# 100kw-DC-Motor-ESC.net
KiCad netlist of a schematic drawn in EAGLE
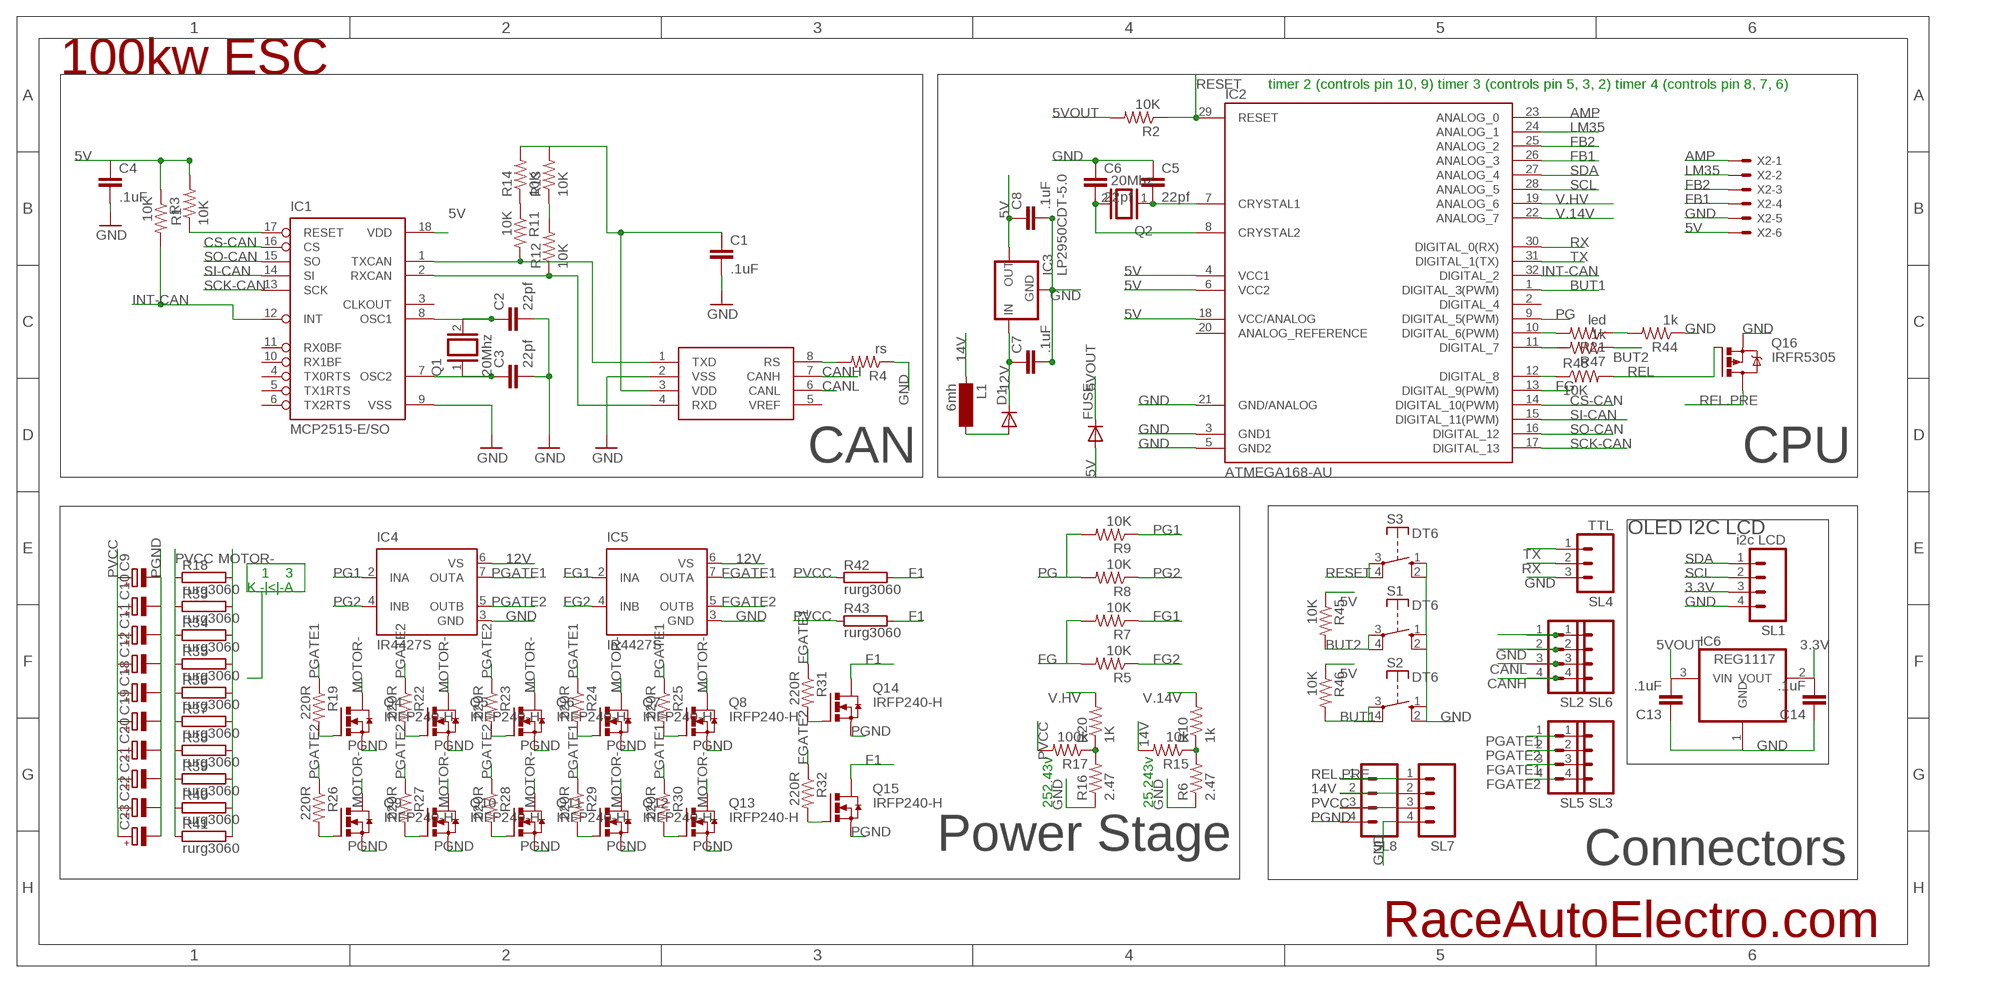
[diagram p0: schematic, sheet 1]

(export (version "E")
  (design (tool "Eeschema 10.0.6"))
  (components
    (comp (ref "C1")
      (value ".1uF")
      (footprint "eagle-import:0805")
      (libsource (lib "eagle-import") (part "CAP0805"))
    )
    (comp (ref "C2")
      (value "22pf")
      (footprint "eagle-import:0805")
      (libsource (lib "eagle-import") (part "CAP0805"))
    )
    (comp (ref "C3")
      (value "22pf")
      (footprint "eagle-import:0805")
      (libsource (lib "eagle-import") (part "CAP0805"))
    )
    (comp (ref "C4")
      (value ".1uF")
      (footprint "eagle-import:1210")
      (libsource (lib "eagle-import") (part "CAP1210"))
    )
    (comp (ref "C5")
      (value "22pf")
      (footprint "eagle-import:0805")
      (libsource (lib "eagle-import") (part "CAP0805"))
    )
    (comp (ref "C6")
      (value "22pf")
      (footprint "eagle-import:0805")
      (libsource (lib "eagle-import") (part "CAP0805"))
    )
    (comp (ref "C7")
      (value ".1uF")
      (footprint "eagle-import:1210")
      (libsource (lib "eagle-import") (part "CAP1210"))
    )
    (comp (ref "C8")
      (value ".1uF")
      (footprint "eagle-import:1210")
      (libsource (lib "eagle-import") (part "CAP1210"))
    )
    (comp (ref "C9")
      (value "CPOL-EUE10-35")
      (footprint "eagle-import:EB35D")
      (libsource (lib "eagle-import") (part "CPOL-EUE10-35"))
    )
    (comp (ref "C10")
      (value "CPOL-EUE10-35")
      (footprint "eagle-import:EB35D")
      (libsource (lib "eagle-import") (part "CPOL-EUE10-35"))
    )
    (comp (ref "C11")
      (value "CPOL-EUE10-35")
      (footprint "eagle-import:EB35D")
      (libsource (lib "eagle-import") (part "CPOL-EUE10-35"))
    )
    (comp (ref "C12")
      (value "CPOL-EUE10-35")
      (footprint "eagle-import:EB35D")
      (libsource (lib "eagle-import") (part "CPOL-EUE10-35"))
    )
    (comp (ref "C13")
      (value ".1uF")
      (footprint "eagle-import:1210")
      (libsource (lib "eagle-import") (part "CAP1210"))
    )
    (comp (ref "C14")
      (value ".1uF")
      (footprint "eagle-import:1210")
      (libsource (lib "eagle-import") (part "CAP1210"))
    )
    (comp (ref "C18")
      (value "CPOL-EUE10-35")
      (footprint "eagle-import:EB35D")
      (libsource (lib "eagle-import") (part "CPOL-EUE10-35"))
    )
    (comp (ref "C19")
      (value "CPOL-EUE10-35")
      (footprint "eagle-import:EB35D")
      (libsource (lib "eagle-import") (part "CPOL-EUE10-35"))
    )
    (comp (ref "C20")
      (value "CPOL-EUE10-35")
      (footprint "eagle-import:EB35D")
      (libsource (lib "eagle-import") (part "CPOL-EUE10-35"))
    )
    (comp (ref "C21")
      (value "CPOL-EUE10-35")
      (footprint "eagle-import:EB35D")
      (libsource (lib "eagle-import") (part "CPOL-EUE10-35"))
    )
    (comp (ref "C22")
      (value "CPOL-EUE10-35")
      (footprint "eagle-import:EB35D")
      (libsource (lib "eagle-import") (part "CPOL-EUE10-35"))
    )
    (comp (ref "C23")
      (value "CPOL-EUE10-35")
      (footprint "eagle-import:EB35D")
      (libsource (lib "eagle-import") (part "CPOL-EUE10-35"))
    )
    (comp (ref "D1")
      (value "DIODE-DO-214AC")
      (footprint "eagle-import:DO-214AC")
      (libsource (lib "eagle-import") (part "DIODE-DO-214AC"))
    )
    (comp (ref "FUSE")
      (value "DIODE-DO-214AC")
      (footprint "eagle-import:DO-214AC")
      (libsource (lib "eagle-import") (part "DIODE-DO-214AC"))
    )
    (comp (ref "IC1")
      (value "MCP2515-E/SO")
      (footprint "eagle-import:SO18L")
      (libsource (lib "eagle-import") (part "MCP2515-E/SO"))
    )
    (comp (ref "IC2")
      (value "ATMEGA168-AU")
      (footprint "eagle-import:TQFP32-08")
      (libsource (lib "eagle-import") (part "ATMEGA168-AU"))
    )
    (comp (ref "IC3")
      (value "LP2950CDT-5.0")
      (footprint "eagle-import:DPACK")
      (libsource (lib "eagle-import") (part "LP2950?CDT-5.0"))
    )
    (comp (ref "IC4")
      (value "IR4427S")
      (footprint "eagle-import:SO08")
      (fields (field (name "MF") "INTERNATIONAL RECTIFIER(IR)") (field (name "MPN") "IR4427STRPBF"))
      (libsource (lib "eagle-import") (part "IR4427S"))
    )
    (comp (ref "IC5")
      (value "IR4427S")
      (footprint "eagle-import:SO08")
      (fields (field (name "MF") "INTERNATIONAL RECTIFIER(IR)") (field (name "MPN") "IR4427STRPBF"))
      (libsource (lib "eagle-import") (part "IR4427S"))
    )
    (comp (ref "IC6")
      (value "REG1117")
      (footprint "eagle-import:SOT223")
      (libsource (lib "eagle-import") (part "REG1117"))
    )
    (comp (ref "L1")
      (value "6mh")
      (footprint "eagle-import:MS85")
      (libsource (lib "eagle-import") (part "MS85"))
    )
    (comp (ref "Q1")
      (value "20Mhz")
      (footprint "eagle-import:QS")
      (libsource (lib "eagle-import") (part "XTAL/S"))
    )
    (comp (ref "Q2")
      (value "20Mhz")
      (footprint "eagle-import:QS")
      (libsource (lib "eagle-import") (part "XTAL/S"))
    )
    (comp (ref "Q4")
      (value "IRFP240-H")
      (footprint "eagle-import:TO247BH")
      (libsource (lib "eagle-import") (part "IRFP240-H"))
    )
    (comp (ref "Q5")
      (value "IRFP240-H")
      (footprint "eagle-import:TO247BH")
      (libsource (lib "eagle-import") (part "IRFP240-H"))
    )
    (comp (ref "Q6")
      (value "IRFP240-H")
      (footprint "eagle-import:TO247BH")
      (libsource (lib "eagle-import") (part "IRFP240-H"))
    )
    (comp (ref "Q7")
      (value "IRFP240-H")
      (footprint "eagle-import:TO247BH")
      (libsource (lib "eagle-import") (part "IRFP240-H"))
    )
    (comp (ref "Q8")
      (value "IRFP240-H")
      (footprint "eagle-import:TO247BH")
      (libsource (lib "eagle-import") (part "IRFP240-H"))
    )
    (comp (ref "Q9")
      (value "IRFP240-H")
      (footprint "eagle-import:TO247BH")
      (libsource (lib "eagle-import") (part "IRFP240-H"))
    )
    (comp (ref "Q10")
      (value "IRFP240-H")
      (footprint "eagle-import:TO247BH")
      (libsource (lib "eagle-import") (part "IRFP240-H"))
    )
    (comp (ref "Q11")
      (value "IRFP240-H")
      (footprint "eagle-import:TO247BH")
      (libsource (lib "eagle-import") (part "IRFP240-H"))
    )
    (comp (ref "Q12")
      (value "IRFP240-H")
      (footprint "eagle-import:TO247BH")
      (libsource (lib "eagle-import") (part "IRFP240-H"))
    )
    (comp (ref "Q13")
      (value "IRFP240-H")
      (footprint "eagle-import:TO247BH")
      (libsource (lib "eagle-import") (part "IRFP240-H"))
    )
    (comp (ref "Q14")
      (value "IRFP240-H")
      (footprint "eagle-import:TO247BH")
      (libsource (lib "eagle-import") (part "IRFP240-H"))
    )
    (comp (ref "Q15")
      (value "IRFP240-H")
      (footprint "eagle-import:TO247BH")
      (libsource (lib "eagle-import") (part "IRFP240-H"))
    )
    (comp (ref "Q16")
      (value "IRFR5305")
      (footprint "eagle-import:D-PAK_TO252AA")
      (libsource (lib "eagle-import") (part "IRF?5305R"))
    )
    (comp (ref "R1")
      (value "10K")
      (footprint "eagle-import:0805")
      (libsource (lib "eagle-import") (part "RESISTOR0805-RES"))
    )
    (comp (ref "R2")
      (value "10K")
      (footprint "eagle-import:1206")
      (libsource (lib "eagle-import") (part "RESISTOR1206"))
    )
    (comp (ref "R3")
      (value "10K")
      (footprint "eagle-import:0805")
      (libsource (lib "eagle-import") (part "RESISTOR0805-RES"))
    )
    (comp (ref "R4")
      (value "rs")
      (footprint "eagle-import:0805")
      (libsource (lib "eagle-import") (part "RESISTOR0805-RES"))
    )
    (comp (ref "R5")
      (value "10K")
      (footprint "eagle-import:0805")
      (libsource (lib "eagle-import") (part "RESISTOR0805-RES"))
    )
    (comp (ref "R6")
      (value "2.47")
      (footprint "eagle-import:0805")
      (libsource (lib "eagle-import") (part "RESISTOR0805-RES"))
    )
    (comp (ref "R7")
      (value "10K")
      (footprint "eagle-import:0805")
      (libsource (lib "eagle-import") (part "RESISTOR0805-RES"))
    )
    (comp (ref "R8")
      (value "10K")
      (footprint "eagle-import:0805")
      (libsource (lib "eagle-import") (part "RESISTOR0805-RES"))
    )
    (comp (ref "R9")
      (value "10K")
      (footprint "eagle-import:0805")
      (libsource (lib "eagle-import") (part "RESISTOR0805-RES"))
    )
    (comp (ref "R10")
      (value "1k")
      (footprint "eagle-import:0805")
      (libsource (lib "eagle-import") (part "RESISTOR0805-RES"))
    )
    (comp (ref "R11")
      (value "10K")
      (footprint "eagle-import:0805")
      (libsource (lib "eagle-import") (part "RESISTOR0805-RES"))
    )
    (comp (ref "R12")
      (value "10K")
      (footprint "eagle-import:0805")
      (libsource (lib "eagle-import") (part "RESISTOR0805-RES"))
    )
    (comp (ref "R13")
      (value "10K")
      (footprint "eagle-import:0805")
      (libsource (lib "eagle-import") (part "RESISTOR0805-RES"))
    )
    (comp (ref "R14")
      (value "10K")
      (footprint "eagle-import:0805")
      (libsource (lib "eagle-import") (part "RESISTOR0805-RES"))
    )
    (comp (ref "R15")
      (value "10k")
      (footprint "eagle-import:0805")
      (libsource (lib "eagle-import") (part "RESISTOR0805-RES"))
    )
    (comp (ref "R16")
      (value "2.47")
      (footprint "eagle-import:0805")
      (libsource (lib "eagle-import") (part "RESISTOR0805-RES"))
    )
    (comp (ref "R17")
      (value "100k")
      (footprint "eagle-import:0805")
      (libsource (lib "eagle-import") (part "RESISTOR0805-RES"))
    )
    (comp (ref "R18")
      (value "rurg3060")
      (footprint "eagle-import:TO-247-2H")
      (libsource (lib "eagle-import") (part "RMG100-H"))
    )
    (comp (ref "R19")
      (value "220R")
      (footprint "eagle-import:0805")
      (libsource (lib "eagle-import") (part "RESISTOR0805-RES"))
    )
    (comp (ref "R20")
      (value "1K")
      (footprint "eagle-import:0805")
      (libsource (lib "eagle-import") (part "RESISTOR0805-RES"))
    )
    (comp (ref "R21")
      (value "led")
      (footprint "eagle-import:1206")
      (libsource (lib "eagle-import") (part "RESISTOR1206"))
    )
    (comp (ref "R22")
      (value "220R")
      (footprint "eagle-import:0805")
      (libsource (lib "eagle-import") (part "RESISTOR0805-RES"))
    )
    (comp (ref "R23")
      (value "220R")
      (footprint "eagle-import:0805")
      (libsource (lib "eagle-import") (part "RESISTOR0805-RES"))
    )
    (comp (ref "R24")
      (value "220R")
      (footprint "eagle-import:0805")
      (libsource (lib "eagle-import") (part "RESISTOR0805-RES"))
    )
    (comp (ref "R25")
      (value "220R")
      (footprint "eagle-import:0805")
      (libsource (lib "eagle-import") (part "RESISTOR0805-RES"))
    )
    (comp (ref "R26")
      (value "220R")
      (footprint "eagle-import:0805")
      (libsource (lib "eagle-import") (part "RESISTOR0805-RES"))
    )
    (comp (ref "R27")
      (value "220R")
      (footprint "eagle-import:0805")
      (libsource (lib "eagle-import") (part "RESISTOR0805-RES"))
    )
    (comp (ref "R28")
      (value "220R")
      (footprint "eagle-import:0805")
      (libsource (lib "eagle-import") (part "RESISTOR0805-RES"))
    )
    (comp (ref "R29")
      (value "220R")
      (footprint "eagle-import:0805")
      (libsource (lib "eagle-import") (part "RESISTOR0805-RES"))
    )
    (comp (ref "R30")
      (value "220R")
      (footprint "eagle-import:0805")
      (libsource (lib "eagle-import") (part "RESISTOR0805-RES"))
    )
    (comp (ref "R31")
      (value "220R")
      (footprint "eagle-import:0805")
      (libsource (lib "eagle-import") (part "RESISTOR0805-RES"))
    )
    (comp (ref "R32")
      (value "220R")
      (footprint "eagle-import:0805")
      (libsource (lib "eagle-import") (part "RESISTOR0805-RES"))
    )
    (comp (ref "R33")
      (value "rurg3060")
      (footprint "eagle-import:TO-247-2H")
      (libsource (lib "eagle-import") (part "RMG100-H"))
    )
    (comp (ref "R34")
      (value "rurg3060")
      (footprint "eagle-import:TO-247-2H")
      (libsource (lib "eagle-import") (part "RMG100-H"))
    )
    (comp (ref "R35")
      (value "rurg3060")
      (footprint "eagle-import:TO-247-2H")
      (libsource (lib "eagle-import") (part "RMG100-H"))
    )
    (comp (ref "R36")
      (value "rurg3060")
      (footprint "eagle-import:TO-247-2H")
      (libsource (lib "eagle-import") (part "RMG100-H"))
    )
    (comp (ref "R37")
      (value "rurg3060")
      (footprint "eagle-import:TO-247-2H")
      (libsource (lib "eagle-import") (part "RMG100-H"))
    )
    (comp (ref "R38")
      (value "rurg3060")
      (footprint "eagle-import:TO-247-2H")
      (libsource (lib "eagle-import") (part "RMG100-H"))
    )
    (comp (ref "R39")
      (value "rurg3060")
      (footprint "eagle-import:TO-247-2H")
      (libsource (lib "eagle-import") (part "RMG100-H"))
    )
    (comp (ref "R40")
      (value "rurg3060")
      (footprint "eagle-import:TO-247-2H")
      (libsource (lib "eagle-import") (part "RMG100-H"))
    )
    (comp (ref "R41")
      (value "rurg3060")
      (footprint "eagle-import:TO-247-2H")
      (libsource (lib "eagle-import") (part "RMG100-H"))
    )
    (comp (ref "R42")
      (value "rurg3060")
      (footprint "eagle-import:TO-247-2H")
      (libsource (lib "eagle-import") (part "RMG100-H"))
    )
    (comp (ref "R43")
      (value "rurg3060")
      (footprint "eagle-import:TO-247-2H")
      (libsource (lib "eagle-import") (part "RMG100-H"))
    )
    (comp (ref "R44")
      (value "1k")
      (footprint "eagle-import:0805")
      (libsource (lib "eagle-import") (part "RESISTOR0805-RES"))
    )
    (comp (ref "R45")
      (value "10K")
      (footprint "eagle-import:0805")
      (libsource (lib "eagle-import") (part "RESISTOR0805-RES"))
    )
    (comp (ref "R46")
      (value "10K")
      (footprint "eagle-import:0805")
      (libsource (lib "eagle-import") (part "RESISTOR0805-RES"))
    )
    (comp (ref "R47")
      (value "1k")
      (footprint "eagle-import:0805")
      (libsource (lib "eagle-import") (part "RESISTOR0805-RES"))
    )
    (comp (ref "R48")
      (value "10K")
      (footprint "eagle-import:0805")
      (libsource (lib "eagle-import") (part "RESISTOR0805-RES"))
    )
    (comp (ref "S1")
      (value "DT6")
      (footprint "eagle-import:DT6")
      (libsource (lib "eagle-import") (part "DT6"))
    )
    (comp (ref "S2")
      (value "DT6")
      (footprint "eagle-import:DT6")
      (libsource (lib "eagle-import") (part "DT6"))
    )
    (comp (ref "S3")
      (value "DT6")
      (footprint "eagle-import:DT6")
      (libsource (lib "eagle-import") (part "DT6"))
    )
    (comp (ref "SL1")
      (value "i2c LCD")
      (footprint "eagle-import:04P")
      (libsource (lib "eagle-import") (part "M04"))
    )
    (comp (ref "SL2")
      (value "M04")
      (footprint "eagle-import:04P")
      (libsource (lib "eagle-import") (part "M04"))
    )
    (comp (ref "SL3")
      (value "M04")
      (footprint "eagle-import:04P")
      (libsource (lib "eagle-import") (part "M04"))
    )
    (comp (ref "SL4")
      (value "TTL")
      (footprint "eagle-import:03P")
      (libsource (lib "eagle-import") (part "M03"))
    )
    (comp (ref "SL5")
      (value "M04")
      (footprint "eagle-import:04P")
      (libsource (lib "eagle-import") (part "M04"))
    )
    (comp (ref "SL6")
      (value "M04")
      (footprint "eagle-import:04P")
      (libsource (lib "eagle-import") (part "M04"))
    )
    (comp (ref "SL7")
      (value "M04")
      (footprint "eagle-import:04P")
      (libsource (lib "eagle-import") (part "M04"))
    )
    (comp (ref "SL8")
      (value "M04")
      (footprint "eagle-import:04P")
      (libsource (lib "eagle-import") (part "M04"))
    )
    (comp (ref "U1")
      (value "MCP2551")
      (footprint "eagle-import:SO08")
      (libsource (lib "eagle-import") (part "MCP2551"))
    )
    (comp (ref "X2")
      (value "22-23-2061")
      (footprint "eagle-import:22-23-2061")
      (fields (field (name "MF") "MOLEX"))
      (libsource (lib "eagle-import") (part "22-23-2061"))
    )
  )
  (nets
    (net (code "1") (name "/3.3V") (class "Default")
      (node (ref "C14") (pin "2") (pinfunction "2_2") (pintype "passive"))
      (node (ref "IC6") (pin "2") (pinfunction "VOUT_2") (pintype "output"))
      (node (ref "SL1") (pin "3") (pinfunction "3_3") (pintype "passive"))
    )
    (net (code "2") (name "/5V") (class "Default")
      (node (ref "C1") (pin "1") (pinfunction "1_1") (pintype "passive"))
      (node (ref "C4") (pin "1") (pinfunction "1_1") (pintype "passive"))
      (node (ref "C8") (pin "1") (pinfunction "1_1") (pintype "passive"))
      (node (ref "FUSE") (pin "A") (pinfunction "A_A") (pintype "passive"))
      (node (ref "IC1") (pin "18") (pinfunction "VDD_18") (pintype "power_in"))
      (node (ref "IC2") (pin "18") (pinfunction "VCC/ANALOG_18") (pintype "passive"))
      (node (ref "IC2") (pin "4") (pinfunction "VCC1_4") (pintype "power_in"))
      (node (ref "IC2") (pin "6") (pinfunction "VCC2_6") (pintype "power_in"))
      (node (ref "IC3") (pin "3") (pinfunction "OUT_3") (pintype "passive"))
      (node (ref "R1") (pin "2") (pinfunction "2_2") (pintype "passive"))
      (node (ref "R13") (pin "2") (pinfunction "2_2") (pintype "passive"))
      (node (ref "R14") (pin "2") (pinfunction "2_2") (pintype "passive"))
      (node (ref "R3") (pin "1") (pinfunction "1_1") (pintype "passive"))
      (node (ref "R45") (pin "1") (pinfunction "1_1") (pintype "passive"))
      (node (ref "R46") (pin "1") (pinfunction "1_1") (pintype "passive"))
      (node (ref "U1") (pin "3") (pinfunction "VDD_3") (pintype "bidirectional"))
      (node (ref "X2") (pin "6") (pinfunction "S_6") (pintype "passive"))
    )
    (net (code "3") (name "/5VOUT") (class "Default")
      (node (ref "C13") (pin "2") (pinfunction "2_2") (pintype "passive"))
      (node (ref "FUSE") (pin "C") (pinfunction "C_C") (pintype "passive"))
      (node (ref "IC6") (pin "3") (pinfunction "VIN_3") (pintype "input"))
      (node (ref "R2") (pin "2") (pinfunction "2_2") (pintype "passive"))
    )
    (net (code "4") (name "/12V") (class "Default")
      (node (ref "C7") (pin "1") (pinfunction "1_1") (pintype "passive"))
      (node (ref "D1") (pin "C") (pinfunction "C_C") (pintype "passive"))
      (node (ref "IC3") (pin "1") (pinfunction "IN_1") (pintype "input"))
      (node (ref "IC4") (pin "6") (pinfunction "VS_6") (pintype "power_in"))
      (node (ref "IC5") (pin "6") (pinfunction "VS_6") (pintype "power_in"))
    )
    (net (code "5") (name "/14V") (class "Default")
      (node (ref "L1") (pin "1") (pinfunction "1_1") (pintype "passive"))
      (node (ref "R15") (pin "2") (pinfunction "2_2") (pintype "passive"))
      (node (ref "SL7") (pin "2") (pinfunction "2_2") (pintype "passive"))
      (node (ref "SL8") (pin "2") (pinfunction "2_2") (pintype "passive"))
    )
    (net (code "6") (name "/AMP") (class "Default")
      (node (ref "IC2") (pin "23") (pinfunction "ANALOG_0_23") (pintype "bidirectional"))
      (node (ref "X2") (pin "1") (pinfunction "S_1") (pintype "passive"))
    )
    (net (code "7") (name "/BUT1") (class "Default")
      (node (ref "IC2") (pin "1") (pinfunction "DIGITAL_3(PWM)_1") (pintype "bidirectional"))
      (node (ref "R46") (pin "2") (pinfunction "2_2") (pintype "passive"))
      (node (ref "S2") (pin "3") (pinfunction "P_3") (pintype "passive"))
      (node (ref "S2") (pin "4") (pinfunction "P_4") (pintype "passive"))
    )
    (net (code "8") (name "/BUT2") (class "Default")
      (node (ref "R45") (pin "2") (pinfunction "2_2") (pintype "passive"))
      (node (ref "R47") (pin "1") (pinfunction "1_1") (pintype "passive"))
      (node (ref "S1") (pin "3") (pinfunction "P_3") (pintype "passive"))
      (node (ref "S1") (pin "4") (pinfunction "P_4") (pintype "passive"))
    )
    (net (code "9") (name "/CANH") (class "Default")
      (node (ref "SL2") (pin "4") (pinfunction "4_4") (pintype "passive"))
      (node (ref "SL6") (pin "4") (pinfunction "4_4") (pintype "passive"))
      (node (ref "U1") (pin "7") (pinfunction "CANH_7") (pintype "bidirectional"))
    )
    (net (code "10") (name "/CANL") (class "Default")
      (node (ref "SL2") (pin "3") (pinfunction "3_3") (pintype "passive"))
      (node (ref "SL6") (pin "3") (pinfunction "3_3") (pintype "passive"))
      (node (ref "U1") (pin "6") (pinfunction "CANL_6") (pintype "bidirectional"))
    )
    (net (code "11") (name "/CS-CAN") (class "Default")
      (node (ref "IC1") (pin "16") (pinfunction "CS_16") (pintype "input"))
      (node (ref "IC2") (pin "14") (pinfunction "DIGITAL_10(PWM)_14") (pintype "bidirectional"))
    )
    (net (code "12") (name "/F1") (class "Default")
      (node (ref "Q14") (pin "D") (pinfunction "D_D") (pintype "passive"))
      (node (ref "Q15") (pin "D") (pinfunction "D_D") (pintype "passive"))
      (node (ref "R42") (pin "2") (pinfunction "2_2") (pintype "passive"))
      (node (ref "R43") (pin "2") (pinfunction "2_2") (pintype "passive"))
    )
    (net (code "13") (name "/FB1") (class "Default")
      (node (ref "IC2") (pin "26") (pinfunction "ANALOG_3_26") (pintype "bidirectional"))
      (node (ref "X2") (pin "4") (pinfunction "S_4") (pintype "passive"))
    )
    (net (code "14") (name "/FB2") (class "Default")
      (node (ref "IC2") (pin "25") (pinfunction "ANALOG_2_25") (pintype "bidirectional"))
      (node (ref "X2") (pin "3") (pinfunction "S_3") (pintype "passive"))
    )
    (net (code "15") (name "/FG") (class "Default")
      (node (ref "IC2") (pin "13") (pinfunction "DIGITAL_9(PWM)_13") (pintype "bidirectional"))
      (node (ref "R5") (pin "2") (pinfunction "2_2") (pintype "passive"))
      (node (ref "R7") (pin "2") (pinfunction "2_2") (pintype "passive"))
    )
    (net (code "16") (name "/FG1") (class "Default")
      (node (ref "IC5") (pin "2") (pinfunction "INA_2") (pintype "input"))
      (node (ref "R7") (pin "1") (pinfunction "1_1") (pintype "passive"))
    )
    (net (code "17") (name "/FG2") (class "Default")
      (node (ref "IC5") (pin "4") (pinfunction "INB_4") (pintype "input"))
      (node (ref "R5") (pin "1") (pinfunction "1_1") (pintype "passive"))
    )
    (net (code "18") (name "/FGATE1") (class "Default")
      (node (ref "IC5") (pin "7") (pinfunction "OUTA_7") (pintype "output"))
      (node (ref "R31") (pin "1") (pinfunction "1_1") (pintype "passive"))
      (node (ref "SL3") (pin "3") (pinfunction "3_3") (pintype "passive"))
      (node (ref "SL5") (pin "3") (pinfunction "3_3") (pintype "passive"))
    )
    (net (code "19") (name "/FGATE2") (class "Default")
      (node (ref "IC5") (pin "5") (pinfunction "OUTB_5") (pintype "output"))
      (node (ref "R32") (pin "1") (pinfunction "1_1") (pintype "passive"))
      (node (ref "SL3") (pin "4") (pinfunction "4_4") (pintype "passive"))
      (node (ref "SL5") (pin "4") (pinfunction "4_4") (pintype "passive"))
    )
    (net (code "20") (name "/INT-CAN") (class "Default")
      (node (ref "IC1") (pin "12") (pinfunction "INT_12") (pintype "output"))
      (node (ref "IC2") (pin "32") (pinfunction "DIGITAL_2_32") (pintype "bidirectional"))
      (node (ref "R3") (pin "2") (pinfunction "2_2") (pintype "passive"))
    )
    (net (code "21") (name "/LM35") (class "Default")
      (node (ref "IC2") (pin "24") (pinfunction "ANALOG_1_24") (pintype "bidirectional"))
      (node (ref "X2") (pin "2") (pinfunction "S_2") (pintype "passive"))
    )
    (net (code "22") (name "/MOTOR-") (class "Default")
      (node (ref "Q10") (pin "D") (pinfunction "D_D") (pintype "passive"))
      (node (ref "Q11") (pin "D") (pinfunction "D_D") (pintype "passive"))
      (node (ref "Q12") (pin "D") (pinfunction "D_D") (pintype "passive"))
      (node (ref "Q13") (pin "D") (pinfunction "D_D") (pintype "passive"))
      (node (ref "Q4") (pin "D") (pinfunction "D_D") (pintype "passive"))
      (node (ref "Q5") (pin "D") (pinfunction "D_D") (pintype "passive"))
      (node (ref "Q6") (pin "D") (pinfunction "D_D") (pintype "passive"))
      (node (ref "Q7") (pin "D") (pinfunction "D_D") (pintype "passive"))
      (node (ref "Q8") (pin "D") (pinfunction "D_D") (pintype "passive"))
      (node (ref "Q9") (pin "D") (pinfunction "D_D") (pintype "passive"))
      (node (ref "R18") (pin "2") (pinfunction "2_2") (pintype "passive"))
      (node (ref "R33") (pin "2") (pinfunction "2_2") (pintype "passive"))
      (node (ref "R34") (pin "2") (pinfunction "2_2") (pintype "passive"))
      (node (ref "R35") (pin "2") (pinfunction "2_2") (pintype "passive"))
      (node (ref "R36") (pin "2") (pinfunction "2_2") (pintype "passive"))
      (node (ref "R37") (pin "2") (pinfunction "2_2") (pintype "passive"))
      (node (ref "R38") (pin "2") (pinfunction "2_2") (pintype "passive"))
      (node (ref "R39") (pin "2") (pinfunction "2_2") (pintype "passive"))
      (node (ref "R40") (pin "2") (pinfunction "2_2") (pintype "passive"))
      (node (ref "R41") (pin "2") (pinfunction "2_2") (pintype "passive"))
    )
    (net (code "23") (name "/PG") (class "Default")
      (node (ref "IC2") (pin "9") (pinfunction "DIGITAL_5(PWM)_9") (pintype "bidirectional"))
      (node (ref "R8") (pin "2") (pinfunction "2_2") (pintype "passive"))
      (node (ref "R9") (pin "2") (pinfunction "2_2") (pintype "passive"))
    )
    (net (code "24") (name "/PG1") (class "Default")
      (node (ref "IC4") (pin "2") (pinfunction "INA_2") (pintype "input"))
      (node (ref "R9") (pin "1") (pinfunction "1_1") (pintype "passive"))
    )
    (net (code "25") (name "/PG2") (class "Default")
      (node (ref "IC4") (pin "4") (pinfunction "INB_4") (pintype "input"))
      (node (ref "R8") (pin "1") (pinfunction "1_1") (pintype "passive"))
    )
    (net (code "26") (name "/PGATE1") (class "Default")
      (node (ref "IC4") (pin "7") (pinfunction "OUTA_7") (pintype "output"))
      (node (ref "R19") (pin "1") (pinfunction "1_1") (pintype "passive"))
      (node (ref "R24") (pin "1") (pinfunction "1_1") (pintype "passive"))
      (node (ref "R25") (pin "1") (pinfunction "1_1") (pintype "passive"))
      (node (ref "R29") (pin "1") (pinfunction "1_1") (pintype "passive"))
      (node (ref "R30") (pin "1") (pinfunction "1_1") (pintype "passive"))
      (node (ref "SL3") (pin "1") (pinfunction "1_1") (pintype "passive"))
      (node (ref "SL5") (pin "1") (pinfunction "1_1") (pintype "passive"))
    )
    (net (code "27") (name "/PGATE2") (class "Default")
      (node (ref "IC4") (pin "5") (pinfunction "OUTB_5") (pintype "output"))
      (node (ref "R22") (pin "1") (pinfunction "1_1") (pintype "passive"))
      (node (ref "R23") (pin "1") (pinfunction "1_1") (pintype "passive"))
      (node (ref "R26") (pin "1") (pinfunction "1_1") (pintype "passive"))
      (node (ref "R27") (pin "1") (pinfunction "1_1") (pintype "passive"))
      (node (ref "R28") (pin "1") (pinfunction "1_1") (pintype "passive"))
      (node (ref "SL3") (pin "2") (pinfunction "2_2") (pintype "passive"))
      (node (ref "SL5") (pin "2") (pinfunction "2_2") (pintype "passive"))
    )
    (net (code "28") (name "/PGND") (class "Default")
      (node (ref "C10") (pin "-") (pinfunction "-_-") (pintype "passive"))
      (node (ref "C11") (pin "-") (pinfunction "-_-") (pintype "passive"))
      (node (ref "C12") (pin "-") (pinfunction "-_-") (pintype "passive"))
      (node (ref "C18") (pin "-") (pinfunction "-_-") (pintype "passive"))
      (node (ref "C19") (pin "-") (pinfunction "-_-") (pintype "passive"))
      (node (ref "C20") (pin "-") (pinfunction "-_-") (pintype "passive"))
      (node (ref "C21") (pin "-") (pinfunction "-_-") (pintype "passive"))
      (node (ref "C22") (pin "-") (pinfunction "-_-") (pintype "passive"))
      (node (ref "C23") (pin "-") (pinfunction "-_-") (pintype "passive"))
      (node (ref "C9") (pin "-") (pinfunction "-_-") (pintype "passive"))
      (node (ref "Q10") (pin "S") (pinfunction "S_S") (pintype "passive"))
      (node (ref "Q11") (pin "S") (pinfunction "S_S") (pintype "passive"))
      (node (ref "Q12") (pin "S") (pinfunction "S_S") (pintype "passive"))
      (node (ref "Q13") (pin "S") (pinfunction "S_S") (pintype "passive"))
      (node (ref "Q14") (pin "S") (pinfunction "S_S") (pintype "passive"))
      (node (ref "Q15") (pin "S") (pinfunction "S_S") (pintype "passive"))
      (node (ref "Q4") (pin "S") (pinfunction "S_S") (pintype "passive"))
      (node (ref "Q5") (pin "S") (pinfunction "S_S") (pintype "passive"))
      (node (ref "Q6") (pin "S") (pinfunction "S_S") (pintype "passive"))
      (node (ref "Q7") (pin "S") (pinfunction "S_S") (pintype "passive"))
      (node (ref "Q8") (pin "S") (pinfunction "S_S") (pintype "passive"))
      (node (ref "Q9") (pin "S") (pinfunction "S_S") (pintype "passive"))
      (node (ref "SL8") (pin "4") (pinfunction "4_4") (pintype "passive"))
    )
    (net (code "29") (name "/PVCC") (class "Default")
      (node (ref "C10") (pin "+") (pinfunction "+_+") (pintype "passive"))
      (node (ref "C11") (pin "+") (pinfunction "+_+") (pintype "passive"))
      (node (ref "C12") (pin "+") (pinfunction "+_+") (pintype "passive"))
      (node (ref "C18") (pin "+") (pinfunction "+_+") (pintype "passive"))
      (node (ref "C19") (pin "+") (pinfunction "+_+") (pintype "passive"))
      (node (ref "C20") (pin "+") (pinfunction "+_+") (pintype "passive"))
      (node (ref "C21") (pin "+") (pinfunction "+_+") (pintype "passive"))
      (node (ref "C22") (pin "+") (pinfunction "+_+") (pintype "passive"))
      (node (ref "C23") (pin "+") (pinfunction "+_+") (pintype "passive"))
      (node (ref "C9") (pin "+") (pinfunction "+_+") (pintype "passive"))
      (node (ref "R17") (pin "2") (pinfunction "2_2") (pintype "passive"))
      (node (ref "R18") (pin "1") (pinfunction "1_1") (pintype "passive"))
      (node (ref "R33") (pin "1") (pinfunction "1_1") (pintype "passive"))
      (node (ref "R34") (pin "1") (pinfunction "1_1") (pintype "passive"))
      (node (ref "R35") (pin "1") (pinfunction "1_1") (pintype "passive"))
      (node (ref "R36") (pin "1") (pinfunction "1_1") (pintype "passive"))
      (node (ref "R37") (pin "1") (pinfunction "1_1") (pintype "passive"))
      (node (ref "R38") (pin "1") (pinfunction "1_1") (pintype "passive"))
      (node (ref "R39") (pin "1") (pinfunction "1_1") (pintype "passive"))
      (node (ref "R40") (pin "1") (pinfunction "1_1") (pintype "passive"))
      (node (ref "R41") (pin "1") (pinfunction "1_1") (pintype "passive"))
      (node (ref "R42") (pin "1") (pinfunction "1_1") (pintype "passive"))
      (node (ref "R43") (pin "1") (pinfunction "1_1") (pintype "passive"))
      (node (ref "SL7") (pin "3") (pinfunction "3_3") (pintype "passive"))
      (node (ref "SL8") (pin "3") (pinfunction "3_3") (pintype "passive"))
    )
    (net (code "30") (name "/REL") (class "Default")
      (node (ref "Q16") (pin "1") (pinfunction "G_1") (pintype "passive"))
      (node (ref "R48") (pin "2") (pinfunction "2_2") (pintype "passive"))
    )
    (net (code "31") (name "/REL.PRE") (class "Default")
      (node (ref "Q16") (pin "4") (pinfunction "D_4") (pintype "passive"))
      (node (ref "SL7") (pin "1") (pinfunction "1_1") (pintype "passive"))
      (node (ref "SL8") (pin "1") (pinfunction "1_1") (pintype "passive"))
    )
    (net (code "32") (name "/RESET") (class "Default")
      (node (ref "IC2") (pin "29") (pinfunction "RESET_29") (pintype "bidirectional"))
      (node (ref "R2") (pin "1") (pinfunction "1_1") (pintype "passive"))
      (node (ref "S3") (pin "3") (pinfunction "P_3") (pintype "passive"))
      (node (ref "S3") (pin "4") (pinfunction "P_4") (pintype "passive"))
    )
    (net (code "33") (name "/RX") (class "Default")
      (node (ref "IC2") (pin "30") (pinfunction "DIGITAL_0(RX)_30") (pintype "bidirectional"))
      (node (ref "SL4") (pin "2") (pinfunction "2_2") (pintype "passive"))
    )
    (net (code "34") (name "/SCK-CAN") (class "Default")
      (node (ref "IC1") (pin "13") (pinfunction "SCK_13") (pintype "input"))
      (node (ref "IC2") (pin "17") (pinfunction "DIGITAL_13_17") (pintype "bidirectional"))
    )
    (net (code "35") (name "/SCL") (class "Default")
      (node (ref "IC2") (pin "28") (pinfunction "ANALOG_5_28") (pintype "bidirectional"))
      (node (ref "SL1") (pin "2") (pinfunction "2_2") (pintype "passive"))
    )
    (net (code "36") (name "/SDA") (class "Default")
      (node (ref "IC2") (pin "27") (pinfunction "ANALOG_4_27") (pintype "bidirectional"))
      (node (ref "SL1") (pin "1") (pinfunction "1_1") (pintype "passive"))
    )
    (net (code "37") (name "/SI-CAN") (class "Default")
      (node (ref "IC1") (pin "14") (pinfunction "SI_14") (pintype "input"))
      (node (ref "IC2") (pin "15") (pinfunction "DIGITAL_11(PWM)_15") (pintype "bidirectional"))
    )
    (net (code "38") (name "/SO-CAN") (class "Default")
      (node (ref "IC1") (pin "15") (pinfunction "SO_15") (pintype "output"))
      (node (ref "IC2") (pin "16") (pinfunction "DIGITAL_12_16") (pintype "bidirectional"))
    )
    (net (code "39") (name "/TX") (class "Default")
      (node (ref "IC2") (pin "31") (pinfunction "DIGITAL_1(TX)_31") (pintype "bidirectional"))
      (node (ref "SL4") (pin "1") (pinfunction "1_1") (pintype "passive"))
    )
    (net (code "40") (name "/V.14V") (class "Default")
      (node (ref "IC2") (pin "22") (pinfunction "ANALOG_7_22") (pintype "passive"))
      (node (ref "R10") (pin "2") (pinfunction "2_2") (pintype "passive"))
    )
    (net (code "41") (name "/V.HV") (class "Default")
      (node (ref "IC2") (pin "19") (pinfunction "ANALOG_6_19") (pintype "passive"))
      (node (ref "R20") (pin "2") (pinfunction "2_2") (pintype "passive"))
    )
    (net (code "42") (name "GND") (class "Default")
      (node (ref "C1") (pin "2") (pinfunction "2_2") (pintype "passive"))
      (node (ref "C13") (pin "1") (pinfunction "1_1") (pintype "passive"))
      (node (ref "C14") (pin "1") (pinfunction "1_1") (pintype "passive"))
      (node (ref "C2") (pin "2") (pinfunction "2_2") (pintype "passive"))
      (node (ref "C3") (pin "2") (pinfunction "2_2") (pintype "passive"))
      (node (ref "C4") (pin "2") (pinfunction "2_2") (pintype "passive"))
      (node (ref "C5") (pin "1") (pinfunction "1_1") (pintype "passive"))
      (node (ref "C6") (pin "1") (pinfunction "1_1") (pintype "passive"))
      (node (ref "C7") (pin "2") (pinfunction "2_2") (pintype "passive"))
      (node (ref "C8") (pin "2") (pinfunction "2_2") (pintype "passive"))
      (node (ref "IC1") (pin "9") (pinfunction "VSS_9") (pintype "power_in"))
      (node (ref "IC2") (pin "21") (pinfunction "GND/ANALOG_21") (pintype "power_in"))
      (node (ref "IC2") (pin "3") (pinfunction "GND1_3") (pintype "power_in"))
      (node (ref "IC2") (pin "5") (pinfunction "GND2_5") (pintype "power_in"))
      (node (ref "IC3") (pin "4") (pinfunction "GND_4") (pintype "input"))
      (node (ref "IC4") (pin "3") (pinfunction "GND_3") (pintype "power_in"))
      (node (ref "IC5") (pin "3") (pinfunction "GND_3") (pintype "power_in"))
      (node (ref "IC6") (pin "1") (pinfunction "GND_1") (pintype "power_in"))
      (node (ref "Q16") (pin "3") (pinfunction "S_3") (pintype "passive"))
      (node (ref "R16") (pin "1") (pinfunction "1_1") (pintype "passive"))
      (node (ref "R4") (pin "1") (pinfunction "1_1") (pintype "passive"))
      (node (ref "R44") (pin "1") (pinfunction "1_1") (pintype "passive"))
      (node (ref "R6") (pin "1") (pinfunction "1_1") (pintype "passive"))
      (node (ref "S1") (pin "1") (pinfunction "S_1") (pintype "passive"))
      (node (ref "S1") (pin "2") (pinfunction "S_2") (pintype "passive"))
      (node (ref "S2") (pin "1") (pinfunction "S_1") (pintype "passive"))
      (node (ref "S2") (pin "2") (pinfunction "S_2") (pintype "passive"))
      (node (ref "S3") (pin "1") (pinfunction "S_1") (pintype "passive"))
      (node (ref "S3") (pin "2") (pinfunction "S_2") (pintype "passive"))
      (node (ref "SL1") (pin "4") (pinfunction "4_4") (pintype "passive"))
      (node (ref "SL2") (pin "2") (pinfunction "2_2") (pintype "passive"))
      (node (ref "SL4") (pin "3") (pinfunction "3_3") (pintype "passive"))
      (node (ref "SL6") (pin "2") (pinfunction "2_2") (pintype "passive"))
      (node (ref "SL7") (pin "4") (pinfunction "4_4") (pintype "passive"))
      (node (ref "U1") (pin "2") (pinfunction "VSS_2") (pintype "bidirectional"))
      (node (ref "X2") (pin "5") (pinfunction "S_5") (pintype "passive"))
    )
    (net (code "43") (name "Net-(D1-PadA)") (class "Default")
      (node (ref "D1") (pin "A") (pinfunction "A_A") (pintype "passive"))
      (node (ref "L1") (pin "2") (pinfunction "2_2") (pintype "passive"))
    )
    (net (code "44") (name "Net-(IC1-OSC1)") (class "Default")
      (node (ref "C2") (pin "1") (pinfunction "1_1") (pintype "passive"))
      (node (ref "IC1") (pin "8") (pinfunction "OSC1_8") (pintype "input"))
      (node (ref "Q1") (pin "2") (pinfunction "2_2") (pintype "passive"))
    )
    (net (code "45") (name "Net-(IC1-OSC2)") (class "Default")
      (node (ref "C3") (pin "1") (pinfunction "1_1") (pintype "passive"))
      (node (ref "IC1") (pin "7") (pinfunction "OSC2_7") (pintype "output"))
      (node (ref "Q1") (pin "1") (pinfunction "1_1") (pintype "passive"))
    )
    (net (code "46") (name "Net-(IC1-RESET)") (class "Default")
      (node (ref "IC1") (pin "17") (pinfunction "RESET_17") (pintype "input"))
      (node (ref "R1") (pin "1") (pinfunction "1_1") (pintype "passive"))
    )
    (net (code "47") (name "Net-(IC1-RXCAN)") (class "Default")
      (node (ref "IC1") (pin "2") (pinfunction "RXCAN_2") (pintype "input"))
      (node (ref "R12") (pin "1") (pinfunction "1_1") (pintype "passive"))
      (node (ref "U1") (pin "4") (pinfunction "RXD_4") (pintype "bidirectional"))
    )
    (net (code "48") (name "Net-(IC1-TXCAN)") (class "Default")
      (node (ref "IC1") (pin "1") (pinfunction "TXCAN_1") (pintype "output"))
      (node (ref "R11") (pin "2") (pinfunction "2_2") (pintype "passive"))
      (node (ref "U1") (pin "1") (pinfunction "TXD_1") (pintype "bidirectional"))
    )
    (net (code "49") (name "Net-(IC2-CRYSTAL1)") (class "Default")
      (node (ref "C5") (pin "2") (pinfunction "2_2") (pintype "passive"))
      (node (ref "IC2") (pin "7") (pinfunction "CRYSTAL1_7") (pintype "bidirectional"))
      (node (ref "Q2") (pin "1") (pinfunction "1_1") (pintype "passive"))
    )
    (net (code "50") (name "Net-(IC2-CRYSTAL2)") (class "Default")
      (node (ref "C6") (pin "2") (pinfunction "2_2") (pintype "passive"))
      (node (ref "IC2") (pin "8") (pinfunction "CRYSTAL2_8") (pintype "bidirectional"))
      (node (ref "Q2") (pin "2") (pinfunction "2_2") (pintype "passive"))
    )
    (net (code "51") (name "Net-(IC2-DIGITAL_6(PWM))") (class "Default")
      (node (ref "IC2") (pin "10") (pinfunction "DIGITAL_6(PWM)_10") (pintype "bidirectional"))
      (node (ref "R21") (pin "2") (pinfunction "2_2") (pintype "passive"))
    )
    (net (code "52") (name "Net-(IC2-DIGITAL_7)") (class "Default")
      (node (ref "IC2") (pin "11") (pinfunction "DIGITAL_7_11") (pintype "bidirectional"))
      (node (ref "R47") (pin "2") (pinfunction "2_2") (pintype "passive"))
    )
    (net (code "53") (name "Net-(IC2-DIGITAL_8)") (class "Default")
      (node (ref "IC2") (pin "12") (pinfunction "DIGITAL_8_12") (pintype "bidirectional"))
      (node (ref "R48") (pin "1") (pinfunction "1_1") (pintype "passive"))
    )
    (net (code "54") (name "Net-(Q4-PadG)") (class "Default")
      (node (ref "Q4") (pin "G") (pinfunction "G_G") (pintype "passive"))
      (node (ref "R19") (pin "2") (pinfunction "2_2") (pintype "passive"))
    )
    (net (code "55") (name "Net-(Q5-PadG)") (class "Default")
      (node (ref "Q5") (pin "G") (pinfunction "G_G") (pintype "passive"))
      (node (ref "R22") (pin "2") (pinfunction "2_2") (pintype "passive"))
    )
    (net (code "56") (name "Net-(Q6-PadG)") (class "Default")
      (node (ref "Q6") (pin "G") (pinfunction "G_G") (pintype "passive"))
      (node (ref "R23") (pin "2") (pinfunction "2_2") (pintype "passive"))
    )
    (net (code "57") (name "Net-(Q7-PadG)") (class "Default")
      (node (ref "Q7") (pin "G") (pinfunction "G_G") (pintype "passive"))
      (node (ref "R24") (pin "2") (pinfunction "2_2") (pintype "passive"))
    )
    (net (code "58") (name "Net-(Q8-PadG)") (class "Default")
      (node (ref "Q8") (pin "G") (pinfunction "G_G") (pintype "passive"))
      (node (ref "R25") (pin "2") (pinfunction "2_2") (pintype "passive"))
    )
    (net (code "59") (name "Net-(Q9-PadG)") (class "Default")
      (node (ref "Q9") (pin "G") (pinfunction "G_G") (pintype "passive"))
      (node (ref "R26") (pin "2") (pinfunction "2_2") (pintype "passive"))
    )
    (net (code "60") (name "Net-(Q10-PadG)") (class "Default")
      (node (ref "Q10") (pin "G") (pinfunction "G_G") (pintype "passive"))
      (node (ref "R27") (pin "2") (pinfunction "2_2") (pintype "passive"))
    )
    (net (code "61") (name "Net-(Q11-PadG)") (class "Default")
      (node (ref "Q11") (pin "G") (pinfunction "G_G") (pintype "passive"))
      (node (ref "R28") (pin "2") (pinfunction "2_2") (pintype "passive"))
    )
    (net (code "62") (name "Net-(Q12-PadG)") (class "Default")
      (node (ref "Q12") (pin "G") (pinfunction "G_G") (pintype "passive"))
      (node (ref "R29") (pin "2") (pinfunction "2_2") (pintype "passive"))
    )
    (net (code "63") (name "Net-(Q13-PadG)") (class "Default")
      (node (ref "Q13") (pin "G") (pinfunction "G_G") (pintype "passive"))
      (node (ref "R30") (pin "2") (pinfunction "2_2") (pintype "passive"))
    )
    (net (code "64") (name "Net-(Q14-PadG)") (class "Default")
      (node (ref "Q14") (pin "G") (pinfunction "G_G") (pintype "passive"))
      (node (ref "R31") (pin "2") (pinfunction "2_2") (pintype "passive"))
    )
    (net (code "65") (name "Net-(Q15-PadG)") (class "Default")
      (node (ref "Q15") (pin "G") (pinfunction "G_G") (pintype "passive"))
      (node (ref "R32") (pin "2") (pinfunction "2_2") (pintype "passive"))
    )
    (net (code "66") (name "Net-(R10-Pad1)") (class "Default")
      (node (ref "R10") (pin "1") (pinfunction "1_1") (pintype "passive"))
      (node (ref "R15") (pin "1") (pinfunction "1_1") (pintype "passive"))
      (node (ref "R6") (pin "2") (pinfunction "2_2") (pintype "passive"))
    )
    (net (code "67") (name "Net-(R11-Pad1)") (class "Default")
      (node (ref "R11") (pin "1") (pinfunction "1_1") (pintype "passive"))
      (node (ref "R14") (pin "1") (pinfunction "1_1") (pintype "passive"))
    )
    (net (code "68") (name "Net-(R12-Pad2)") (class "Default")
      (node (ref "R12") (pin "2") (pinfunction "2_2") (pintype "passive"))
      (node (ref "R13") (pin "1") (pinfunction "1_1") (pintype "passive"))
    )
    (net (code "69") (name "Net-(R16-Pad2)") (class "Default")
      (node (ref "R16") (pin "2") (pinfunction "2_2") (pintype "passive"))
      (node (ref "R17") (pin "1") (pinfunction "1_1") (pintype "passive"))
      (node (ref "R20") (pin "1") (pinfunction "1_1") (pintype "passive"))
    )
    (net (code "70") (name "Net-(R21-Pad1)") (class "Default")
      (node (ref "R21") (pin "1") (pinfunction "1_1") (pintype "passive"))
      (node (ref "R44") (pin "2") (pinfunction "2_2") (pintype "passive"))
    )
    (net (code "71") (name "Net-(SL2-Pad1)") (class "Default")
      (node (ref "SL2") (pin "1") (pinfunction "1_1") (pintype "passive"))
      (node (ref "SL6") (pin "1") (pinfunction "1_1") (pintype "passive"))
    )
    (net (code "72") (name "Net-(U1-RS)") (class "Default")
      (node (ref "R4") (pin "2") (pinfunction "2_2") (pintype "passive"))
      (node (ref "U1") (pin "8") (pinfunction "RS_8") (pintype "bidirectional"))
    )
    (net (code "73") (name "unconnected-(IC1-CLKOUT-Pad3)") (class "Default")
      (node (ref "IC1") (pin "3") (pinfunction "CLKOUT_3") (pintype "output"))
    )
    (net (code "74") (name "unconnected-(IC1-RX0BF-Pad11)") (class "Default")
      (node (ref "IC1") (pin "11") (pinfunction "RX0BF_11") (pintype "output"))
    )
    (net (code "75") (name "unconnected-(IC1-RX1BF-Pad10)") (class "Default")
      (node (ref "IC1") (pin "10") (pinfunction "RX1BF_10") (pintype "output"))
    )
    (net (code "76") (name "unconnected-(IC1-TX0RTS-Pad4)") (class "Default")
      (node (ref "IC1") (pin "4") (pinfunction "TX0RTS_4") (pintype "input"))
    )
    (net (code "77") (name "unconnected-(IC1-TX1RTS-Pad5)") (class "Default")
      (node (ref "IC1") (pin "5") (pinfunction "TX1RTS_5") (pintype "input"))
    )
    (net (code "78") (name "unconnected-(IC1-TX2RTS-Pad6)") (class "Default")
      (node (ref "IC1") (pin "6") (pinfunction "TX2RTS_6") (pintype "input"))
    )
    (net (code "79") (name "unconnected-(IC2-ANALOG_REFERENCE-Pad20)") (class "Default")
      (node (ref "IC2") (pin "20") (pinfunction "ANALOG_REFERENCE_20") (pintype "passive"))
    )
    (net (code "80") (name "unconnected-(IC2-DIGITAL_4-Pad2)") (class "Default")
      (node (ref "IC2") (pin "2") (pinfunction "DIGITAL_4_2") (pintype "bidirectional"))
    )
    (net (code "81") (name "unconnected-(U1-VREF-Pad5)") (class "Default")
      (node (ref "U1") (pin "5") (pinfunction "VREF_5") (pintype "bidirectional"))
    )
  )
)
